# dast.net
KiCad netlist of a schematic drawn in Altium Designer
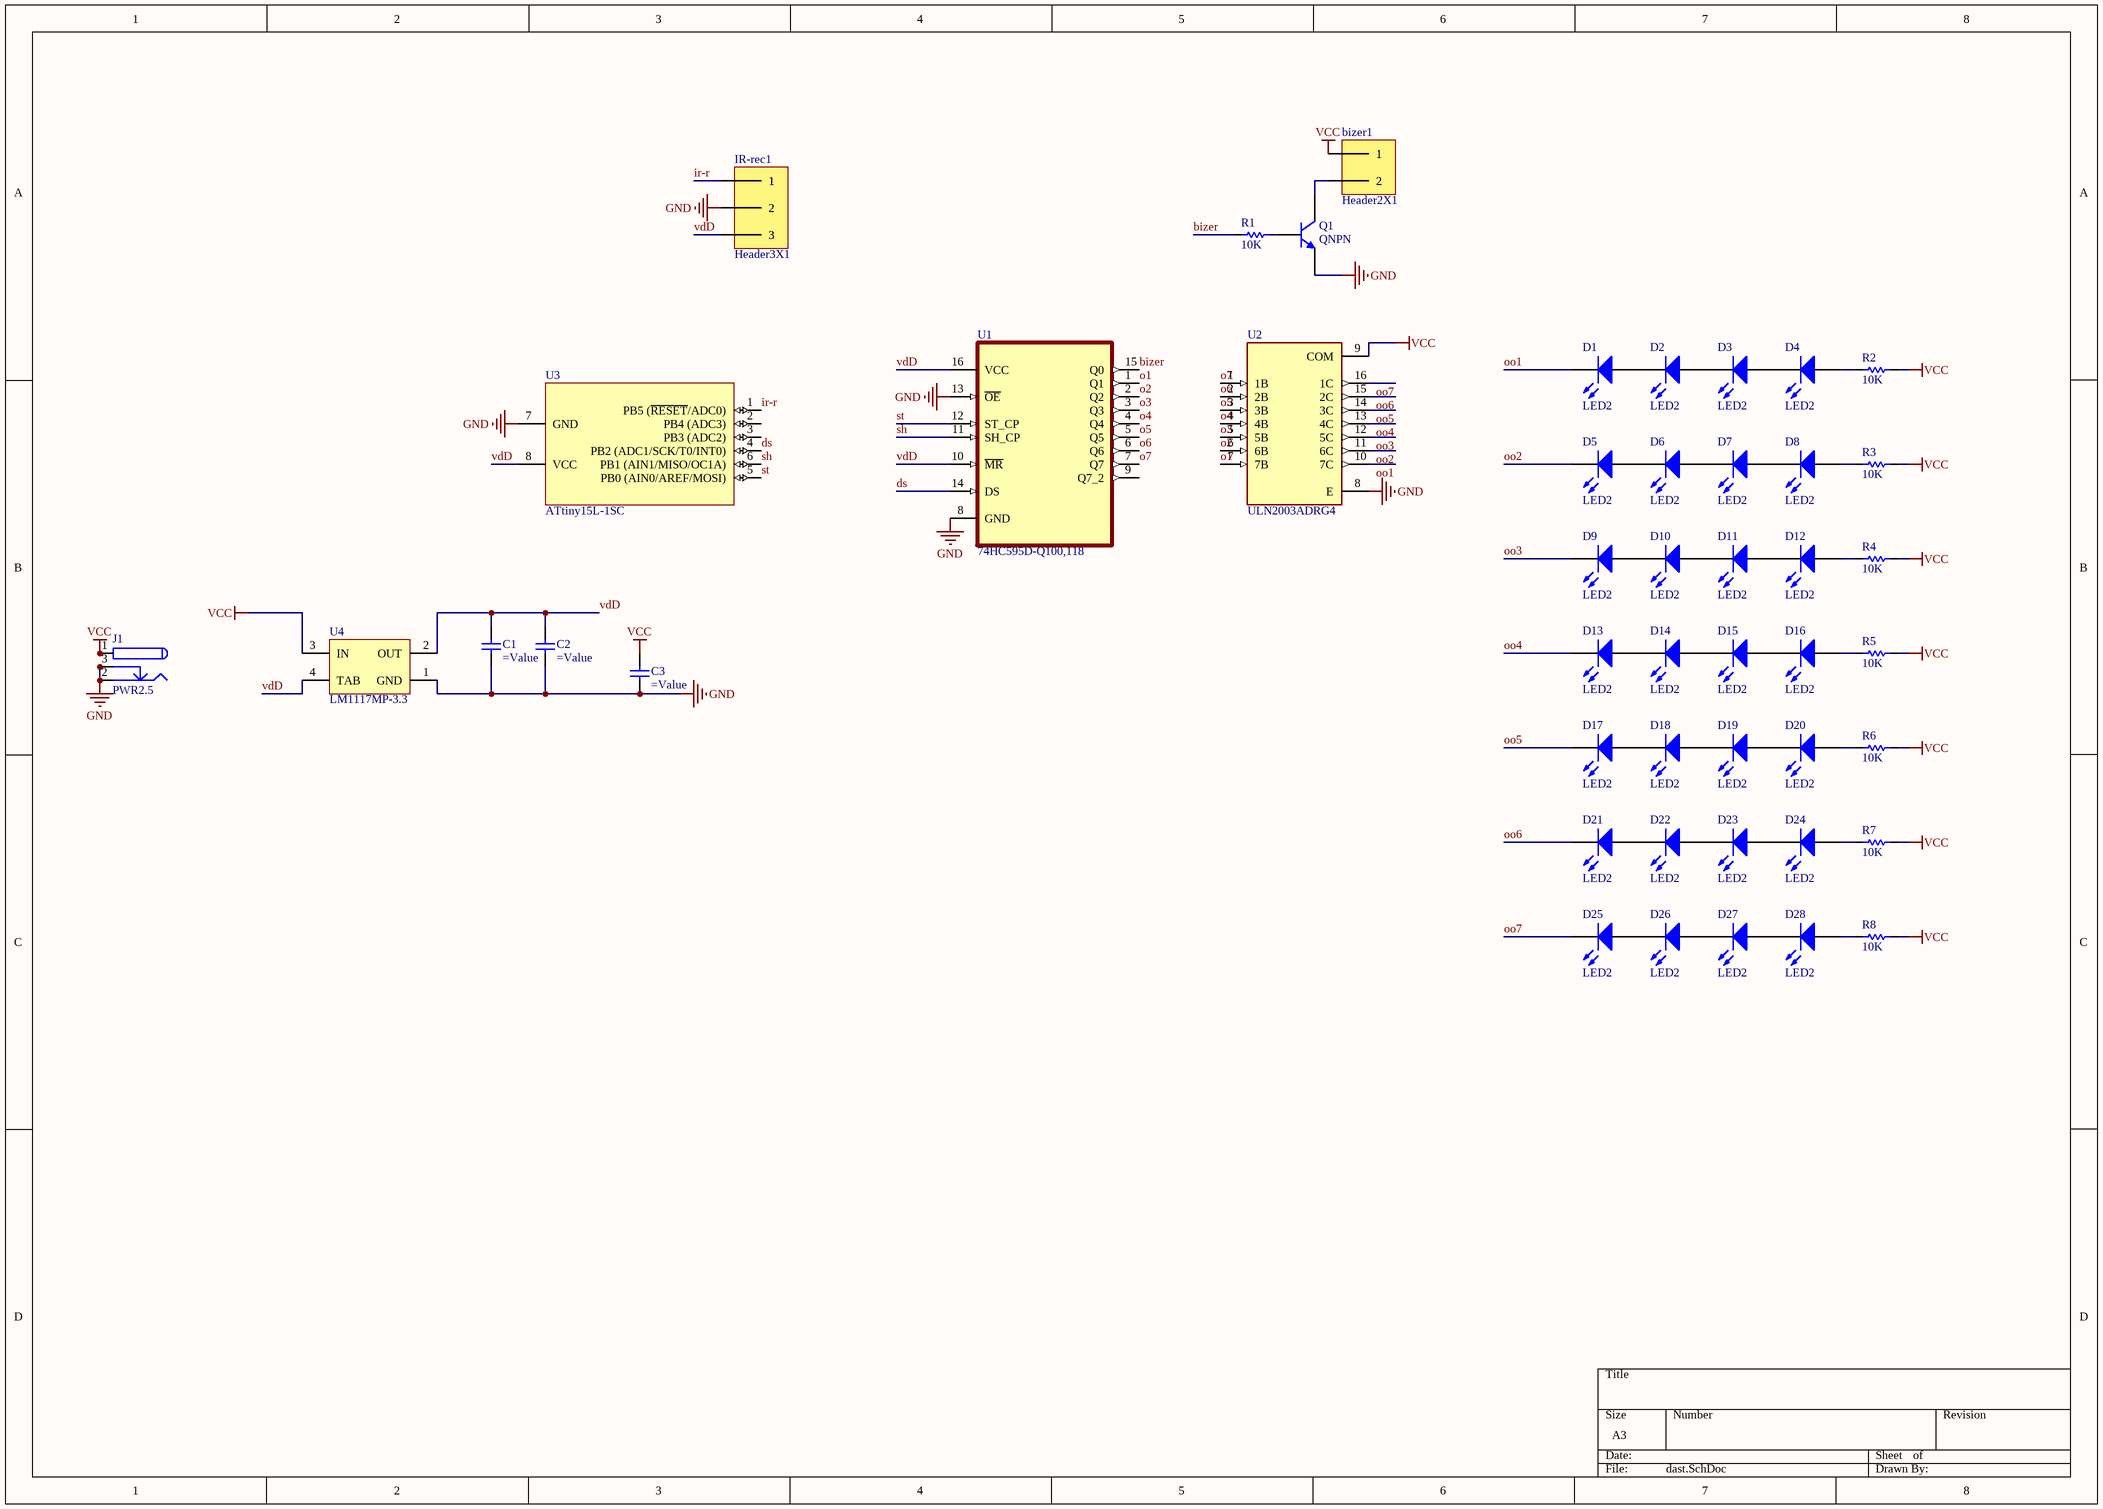
[diagram p0: dast.SchDoc]

(export (version "E")
  (design (tool "Eeschema 10.0.6"))
  (components
    (comp (ref "bizer1")
      (value "Header2X1")
      (footprint "Header 2X1")
      (libsource (lib "AltiumLib1") (part "Header2X1"))
    )
    (comp (ref "C1")
      (value "~")
      (footprint "CAP 1206")
      (description "Capacitor")
      (libsource (lib "AltiumLib1") (part "Capacitor"))
    )
    (comp (ref "C2")
      (value "~")
      (footprint "CAP 1206")
      (description "Capacitor")
      (libsource (lib "AltiumLib1") (part "Capacitor"))
    )
    (comp (ref "C3")
      (value "~")
      (footprint "CAP 1206")
      (description "Capacitor")
      (libsource (lib "AltiumLib1") (part "Capacitor"))
    )
    (comp (ref "D1")
      (value "LED2")
      (footprint "3.2X1.6X1.1")
      (description "Typical RED, GREEN, YELLOW, AMBER GaAs LED")
      (fields (field (name "PUBLISHER") "Altium Limited"))
      (libsource (lib "Miscellaneous Devices") (part "LED2"))
    )
    (comp (ref "D2")
      (value "LED2")
      (footprint "3.2X1.6X1.1")
      (description "Typical RED, GREEN, YELLOW, AMBER GaAs LED")
      (fields (field (name "PUBLISHER") "Altium Limited"))
      (libsource (lib "Miscellaneous Devices") (part "LED2"))
    )
    (comp (ref "D3")
      (value "LED2")
      (footprint "3.2X1.6X1.1")
      (description "Typical RED, GREEN, YELLOW, AMBER GaAs LED")
      (fields (field (name "PUBLISHER") "Altium Limited"))
      (libsource (lib "Miscellaneous Devices") (part "LED2"))
    )
    (comp (ref "D4")
      (value "LED2")
      (footprint "3.2X1.6X1.1")
      (description "Typical RED, GREEN, YELLOW, AMBER GaAs LED")
      (fields (field (name "PUBLISHER") "Altium Limited"))
      (libsource (lib "Miscellaneous Devices") (part "LED2"))
    )
    (comp (ref "D5")
      (value "LED2")
      (footprint "3.2X1.6X1.1")
      (description "Typical RED, GREEN, YELLOW, AMBER GaAs LED")
      (fields (field (name "PUBLISHER") "Altium Limited"))
      (libsource (lib "Miscellaneous Devices") (part "LED2"))
    )
    (comp (ref "D6")
      (value "LED2")
      (footprint "3.2X1.6X1.1")
      (description "Typical RED, GREEN, YELLOW, AMBER GaAs LED")
      (fields (field (name "PUBLISHER") "Altium Limited"))
      (libsource (lib "Miscellaneous Devices") (part "LED2"))
    )
    (comp (ref "D7")
      (value "LED2")
      (footprint "3.2X1.6X1.1")
      (description "Typical RED, GREEN, YELLOW, AMBER GaAs LED")
      (fields (field (name "PUBLISHER") "Altium Limited"))
      (libsource (lib "Miscellaneous Devices") (part "LED2"))
    )
    (comp (ref "D8")
      (value "LED2")
      (footprint "3.2X1.6X1.1")
      (description "Typical RED, GREEN, YELLOW, AMBER GaAs LED")
      (fields (field (name "PUBLISHER") "Altium Limited"))
      (libsource (lib "Miscellaneous Devices") (part "LED2"))
    )
    (comp (ref "D9")
      (value "LED2")
      (footprint "3.2X1.6X1.1")
      (description "Typical RED, GREEN, YELLOW, AMBER GaAs LED")
      (fields (field (name "PUBLISHER") "Altium Limited"))
      (libsource (lib "Miscellaneous Devices") (part "LED2"))
    )
    (comp (ref "D10")
      (value "LED2")
      (footprint "3.2X1.6X1.1")
      (description "Typical RED, GREEN, YELLOW, AMBER GaAs LED")
      (fields (field (name "PUBLISHER") "Altium Limited"))
      (libsource (lib "Miscellaneous Devices") (part "LED2"))
    )
    (comp (ref "D11")
      (value "LED2")
      (footprint "3.2X1.6X1.1")
      (description "Typical RED, GREEN, YELLOW, AMBER GaAs LED")
      (fields (field (name "PUBLISHER") "Altium Limited"))
      (libsource (lib "Miscellaneous Devices") (part "LED2"))
    )
    (comp (ref "D12")
      (value "LED2")
      (footprint "3.2X1.6X1.1")
      (description "Typical RED, GREEN, YELLOW, AMBER GaAs LED")
      (fields (field (name "PUBLISHER") "Altium Limited"))
      (libsource (lib "Miscellaneous Devices") (part "LED2"))
    )
    (comp (ref "D13")
      (value "LED2")
      (footprint "3.2X1.6X1.1")
      (description "Typical RED, GREEN, YELLOW, AMBER GaAs LED")
      (fields (field (name "PUBLISHER") "Altium Limited"))
      (libsource (lib "Miscellaneous Devices") (part "LED2"))
    )
    (comp (ref "D14")
      (value "LED2")
      (footprint "3.2X1.6X1.1")
      (description "Typical RED, GREEN, YELLOW, AMBER GaAs LED")
      (fields (field (name "PUBLISHER") "Altium Limited"))
      (libsource (lib "Miscellaneous Devices") (part "LED2"))
    )
    (comp (ref "D15")
      (value "LED2")
      (footprint "3.2X1.6X1.1")
      (description "Typical RED, GREEN, YELLOW, AMBER GaAs LED")
      (fields (field (name "PUBLISHER") "Altium Limited"))
      (libsource (lib "Miscellaneous Devices") (part "LED2"))
    )
    (comp (ref "D16")
      (value "LED2")
      (footprint "3.2X1.6X1.1")
      (description "Typical RED, GREEN, YELLOW, AMBER GaAs LED")
      (fields (field (name "PUBLISHER") "Altium Limited"))
      (libsource (lib "Miscellaneous Devices") (part "LED2"))
    )
    (comp (ref "D17")
      (value "LED2")
      (footprint "3.2X1.6X1.1")
      (description "Typical RED, GREEN, YELLOW, AMBER GaAs LED")
      (fields (field (name "PUBLISHER") "Altium Limited"))
      (libsource (lib "Miscellaneous Devices") (part "LED2"))
    )
    (comp (ref "D18")
      (value "LED2")
      (footprint "3.2X1.6X1.1")
      (description "Typical RED, GREEN, YELLOW, AMBER GaAs LED")
      (fields (field (name "PUBLISHER") "Altium Limited"))
      (libsource (lib "Miscellaneous Devices") (part "LED2"))
    )
    (comp (ref "D19")
      (value "LED2")
      (footprint "3.2X1.6X1.1")
      (description "Typical RED, GREEN, YELLOW, AMBER GaAs LED")
      (fields (field (name "PUBLISHER") "Altium Limited"))
      (libsource (lib "Miscellaneous Devices") (part "LED2"))
    )
    (comp (ref "D20")
      (value "LED2")
      (footprint "3.2X1.6X1.1")
      (description "Typical RED, GREEN, YELLOW, AMBER GaAs LED")
      (fields (field (name "PUBLISHER") "Altium Limited"))
      (libsource (lib "Miscellaneous Devices") (part "LED2"))
    )
    (comp (ref "D21")
      (value "LED2")
      (footprint "3.2X1.6X1.1")
      (description "Typical RED, GREEN, YELLOW, AMBER GaAs LED")
      (fields (field (name "PUBLISHER") "Altium Limited"))
      (libsource (lib "Miscellaneous Devices") (part "LED2"))
    )
    (comp (ref "D22")
      (value "LED2")
      (footprint "3.2X1.6X1.1")
      (description "Typical RED, GREEN, YELLOW, AMBER GaAs LED")
      (fields (field (name "PUBLISHER") "Altium Limited"))
      (libsource (lib "Miscellaneous Devices") (part "LED2"))
    )
    (comp (ref "D23")
      (value "LED2")
      (footprint "3.2X1.6X1.1")
      (description "Typical RED, GREEN, YELLOW, AMBER GaAs LED")
      (fields (field (name "PUBLISHER") "Altium Limited"))
      (libsource (lib "Miscellaneous Devices") (part "LED2"))
    )
    (comp (ref "D24")
      (value "LED2")
      (footprint "3.2X1.6X1.1")
      (description "Typical RED, GREEN, YELLOW, AMBER GaAs LED")
      (fields (field (name "PUBLISHER") "Altium Limited"))
      (libsource (lib "Miscellaneous Devices") (part "LED2"))
    )
    (comp (ref "D25")
      (value "LED2")
      (footprint "3.2X1.6X1.1")
      (description "Typical RED, GREEN, YELLOW, AMBER GaAs LED")
      (fields (field (name "PUBLISHER") "Altium Limited"))
      (libsource (lib "Miscellaneous Devices") (part "LED2"))
    )
    (comp (ref "D26")
      (value "LED2")
      (footprint "3.2X1.6X1.1")
      (description "Typical RED, GREEN, YELLOW, AMBER GaAs LED")
      (fields (field (name "PUBLISHER") "Altium Limited"))
      (libsource (lib "Miscellaneous Devices") (part "LED2"))
    )
    (comp (ref "D27")
      (value "LED2")
      (footprint "3.2X1.6X1.1")
      (description "Typical RED, GREEN, YELLOW, AMBER GaAs LED")
      (fields (field (name "PUBLISHER") "Altium Limited"))
      (libsource (lib "Miscellaneous Devices") (part "LED2"))
    )
    (comp (ref "D28")
      (value "LED2")
      (footprint "3.2X1.6X1.1")
      (description "Typical RED, GREEN, YELLOW, AMBER GaAs LED")
      (fields (field (name "PUBLISHER") "Altium Limited"))
      (libsource (lib "Miscellaneous Devices") (part "LED2"))
    )
    (comp (ref "IR-rec1")
      (value "Header3X1")
      (footprint "HEADER 3X1")
      (libsource (lib "AltiumLib1") (part "Header3X1"))
    )
    (comp (ref "J1")
      (value "PWR2.5")
      (footprint "KLD-0202")
      (description "Low Voltage Power Supply Connector")
      (fields (field (name "PUBLISHER") "Altium Limited"))
      (libsource (lib "Miscellaneous Connectors") (part "PWR2.5"))
    )
    (comp (ref "Q1")
      (value "QNPN")
      (footprint "SOT-23B_L")
      (description "NPN Bipolar Transistor")
      (fields (field (name "PUBLISHER") "Altium Limited"))
      (libsource (lib "Miscellaneous Devices") (part "QNPN"))
    )
    (comp (ref "R1")
      (value "10K")
      (footprint "RES 1206 (3216X08L)")
      (description "Resistor")
      (fields (field (name "TOLERANCE") "5%") (field (name "POWER") "1/4 W"))
      (libsource (lib "AltiumLib1") (part "Resistor"))
    )
    (comp (ref "R2")
      (value "10K")
      (footprint "RES 1206 (3216X08L)")
      (description "Resistor")
      (fields (field (name "TOLERANCE") "5%") (field (name "POWER") "1/4 W"))
      (libsource (lib "AltiumLib1") (part "Resistor"))
    )
    (comp (ref "R3")
      (value "10K")
      (footprint "RES 1206 (3216X08L)")
      (description "Resistor")
      (fields (field (name "TOLERANCE") "5%") (field (name "POWER") "1/4 W"))
      (libsource (lib "AltiumLib1") (part "Resistor"))
    )
    (comp (ref "R4")
      (value "10K")
      (footprint "RES 1206 (3216X08L)")
      (description "Resistor")
      (fields (field (name "TOLERANCE") "5%") (field (name "POWER") "1/4 W"))
      (libsource (lib "AltiumLib1") (part "Resistor"))
    )
    (comp (ref "R5")
      (value "10K")
      (footprint "RES 1206 (3216X08L)")
      (description "Resistor")
      (fields (field (name "TOLERANCE") "5%") (field (name "POWER") "1/4 W"))
      (libsource (lib "AltiumLib1") (part "Resistor"))
    )
    (comp (ref "R6")
      (value "10K")
      (footprint "RES 1206 (3216X08L)")
      (description "Resistor")
      (fields (field (name "TOLERANCE") "5%") (field (name "POWER") "1/4 W"))
      (libsource (lib "AltiumLib1") (part "Resistor"))
    )
    (comp (ref "R7")
      (value "10K")
      (footprint "RES 1206 (3216X08L)")
      (description "Resistor")
      (fields (field (name "TOLERANCE") "5%") (field (name "POWER") "1/4 W"))
      (libsource (lib "AltiumLib1") (part "Resistor"))
    )
    (comp (ref "R8")
      (value "10K")
      (footprint "RES 1206 (3216X08L)")
      (description "Resistor")
      (fields (field (name "TOLERANCE") "5%") (field (name "POWER") "1/4 W"))
      (libsource (lib "AltiumLib1") (part "Resistor"))
    )
    (comp (ref "U1")
      (value "74HC595D-Q100,118")
      (footprint "SOIC127P600X175-16N")
      (description "Shift Shift Register 1 Element 8 Bit 16-SO")
      (fields (field (name "MF") "Nexperia USA"))
      (libsource (lib "74HC595D-Q100_118") (part "74HC595D-Q100,118"))
    )
    (comp (ref "U2")
      (value "ULN2003ADRG4")
      (footprint "SOIC127P600X175-16N")
      (description "50-V, 7-ch darlington transistor array, -20C to 70C 16-SOIC -40 to 70")
      (libsource (lib "ULN2003ADRG4") (part "ULN2003ADRG4"))
    )
    (comp (ref "U3")
      (value "ATtiny15L-1SC")
      (footprint "8S2_N")
      (description "8-Bit AVR Microcontroller with 1K Byte of Flash Memory")
      (fields (field (name "PUBLISHER") "Altium Limited"))
      (libsource (lib "Atmel Microcontroller 8-Bit AVR") (part "ATtiny15L-1SC"))
    )
    (comp (ref "U4")
      (value "LM1117MP-3.3")
      (footprint "MP04A_N")
      (description "800mA Low-Dropout Linear Regulator")
      (fields
        (field (name "MANUFACTURER") "National Semiconductor")
        (field (name "DIGIKEYPARTNUMBER") "LM1117MP-3.3CT-ND")
        (field (name "PUBLISHER") "Altium Limited")
      )
      (libsource (lib "NSC LDO") (part "LM1117MP-3.3"))
    )
  )
  (nets
    (net (code "1") (name "/bizer") (class "Default")
      (node (ref "R1") (pin "1") (pinfunction "1_1") (pintype "passive"))
      (node (ref "U1") (pin "15") (pinfunction "Q0_15") (pintype "output"))
    )
    (net (code "2") (name "/ds") (class "Default")
      (node (ref "U1") (pin "14") (pinfunction "DS_14") (pintype "input"))
      (node (ref "U3") (pin "4") (pinfunction "PB2_(ADC1/SCK/T0/INT0)_4") (pintype "bidirectional"))
    )
    (net (code "3") (name "/ir-r") (class "Default")
      (node (ref "IR-rec1") (pin "1") (pinfunction "1_1") (pintype "passive"))
      (node (ref "U3") (pin "1") (pinfunction "PB5_(~{RESET}/ADC0)_1") (pintype "bidirectional"))
    )
    (net (code "4") (name "/o1") (class "Default")
      (node (ref "U1") (pin "1") (pinfunction "Q1_1") (pintype "output"))
      (node (ref "U2") (pin "7") (pinfunction "7B_7") (pintype "input"))
    )
    (net (code "5") (name "/o2") (class "Default")
      (node (ref "U1") (pin "2") (pinfunction "Q2_2") (pintype "output"))
      (node (ref "U2") (pin "6") (pinfunction "6B_6") (pintype "input"))
    )
    (net (code "6") (name "/o3") (class "Default")
      (node (ref "U1") (pin "3") (pinfunction "Q3_3") (pintype "output"))
      (node (ref "U2") (pin "5") (pinfunction "5B_5") (pintype "input"))
    )
    (net (code "7") (name "/o4") (class "Default")
      (node (ref "U1") (pin "4") (pinfunction "Q4_4") (pintype "output"))
      (node (ref "U2") (pin "4") (pinfunction "4B_4") (pintype "input"))
    )
    (net (code "8") (name "/o5") (class "Default")
      (node (ref "U1") (pin "5") (pinfunction "Q5_5") (pintype "output"))
      (node (ref "U2") (pin "3") (pinfunction "3B_3") (pintype "input"))
    )
    (net (code "9") (name "/o6") (class "Default")
      (node (ref "U1") (pin "6") (pinfunction "Q6_6") (pintype "output"))
      (node (ref "U2") (pin "2") (pinfunction "2B_2") (pintype "input"))
    )
    (net (code "10") (name "/o7") (class "Default")
      (node (ref "U1") (pin "7") (pinfunction "Q7_7") (pintype "output"))
      (node (ref "U2") (pin "1") (pinfunction "1B_1") (pintype "input"))
    )
    (net (code "11") (name "/oo1") (class "Default")
      (node (ref "D1") (pin "2") (pinfunction "K_2") (pintype "passive"))
      (node (ref "U2") (pin "10") (pinfunction "7C_10") (pintype "output"))
    )
    (net (code "12") (name "/oo2") (class "Default")
      (node (ref "D5") (pin "2") (pinfunction "K_2") (pintype "passive"))
      (node (ref "U2") (pin "11") (pinfunction "6C_11") (pintype "output"))
    )
    (net (code "13") (name "/oo3") (class "Default")
      (node (ref "D9") (pin "2") (pinfunction "K_2") (pintype "passive"))
      (node (ref "U2") (pin "12") (pinfunction "5C_12") (pintype "output"))
    )
    (net (code "14") (name "/oo4") (class "Default")
      (node (ref "D13") (pin "2") (pinfunction "K_2") (pintype "passive"))
      (node (ref "U2") (pin "13") (pinfunction "4C_13") (pintype "output"))
    )
    (net (code "15") (name "/oo5") (class "Default")
      (node (ref "D17") (pin "2") (pinfunction "K_2") (pintype "passive"))
      (node (ref "U2") (pin "14") (pinfunction "3C_14") (pintype "output"))
    )
    (net (code "16") (name "/oo6") (class "Default")
      (node (ref "D21") (pin "2") (pinfunction "K_2") (pintype "passive"))
      (node (ref "U2") (pin "15") (pinfunction "2C_15") (pintype "output"))
    )
    (net (code "17") (name "/oo7") (class "Default")
      (node (ref "D25") (pin "2") (pinfunction "K_2") (pintype "passive"))
      (node (ref "U2") (pin "16") (pinfunction "1C_16") (pintype "output"))
    )
    (net (code "18") (name "/sh") (class "Default")
      (node (ref "U1") (pin "11") (pinfunction "SH_CP_11") (pintype "input"))
      (node (ref "U3") (pin "6") (pinfunction "PB1_(AIN1/MISO/OC1A)_6") (pintype "bidirectional"))
    )
    (net (code "19") (name "/st") (class "Default")
      (node (ref "U1") (pin "12") (pinfunction "ST_CP_12") (pintype "input"))
      (node (ref "U3") (pin "5") (pinfunction "PB0_(AIN0/AREF/MOSI)_5") (pintype "bidirectional"))
    )
    (net (code "20") (name "/vdD") (class "Default")
      (node (ref "C1") (pin "2") (pinfunction "-_2") (pintype "passive"))
      (node (ref "C2") (pin "2") (pinfunction "-_2") (pintype "passive"))
      (node (ref "IR-rec1") (pin "3") (pinfunction "3_3") (pintype "passive"))
      (node (ref "U1") (pin "10") (pinfunction "~{MR}_10") (pintype "input"))
      (node (ref "U1") (pin "16") (pinfunction "VCC_16") (pintype "power_in"))
      (node (ref "U3") (pin "8") (pinfunction "VCC_8") (pintype "power_in"))
      (node (ref "U4") (pin "2") (pinfunction "OUT_2") (pintype "power_in"))
      (node (ref "U4") (pin "4") (pinfunction "TAB_4") (pintype "power_in"))
    )
    (net (code "21") (name "GND") (class "Default")
      (node (ref "C1") (pin "1") (pinfunction "+_1") (pintype "passive"))
      (node (ref "C2") (pin "1") (pinfunction "+_1") (pintype "passive"))
      (node (ref "C3") (pin "1") (pinfunction "+_1") (pintype "passive"))
      (node (ref "IR-rec1") (pin "2") (pinfunction "2_2") (pintype "passive"))
      (node (ref "J1") (pin "2") (pinfunction "2_2") (pintype "power_in"))
      (node (ref "J1") (pin "2A") (pinfunction "2A_2A") (pintype "power_in"))
      (node (ref "J1") (pin "2B") (pinfunction "2B_2B") (pintype "power_in"))
      (node (ref "J1") (pin "3") (pinfunction "3_3") (pintype "power_in"))
      (node (ref "J1") (pin "3A") (pinfunction "3A_3A") (pintype "power_in"))
      (node (ref "J1") (pin "3B") (pinfunction "3B_3B") (pintype "power_in"))
      (node (ref "Q1") (pin "3") (pinfunction "E_3") (pintype "passive"))
      (node (ref "U1") (pin "13") (pinfunction "~{OE}_13") (pintype "input"))
      (node (ref "U1") (pin "8") (pinfunction "GND_8") (pintype "passive"))
      (node (ref "U2") (pin "8") (pinfunction "E_8") (pintype "passive"))
      (node (ref "U3") (pin "7") (pinfunction "GND_7") (pintype "power_in"))
      (node (ref "U4") (pin "1") (pinfunction "GND_1") (pintype "power_in"))
    )
    (net (code "22") (name "Net-(D1-A)") (class "Default")
      (node (ref "D1") (pin "1") (pinfunction "A_1") (pintype "passive"))
      (node (ref "D2") (pin "2") (pinfunction "K_2") (pintype "passive"))
    )
    (net (code "23") (name "Net-(D2-A)") (class "Default")
      (node (ref "D2") (pin "1") (pinfunction "A_1") (pintype "passive"))
      (node (ref "D3") (pin "2") (pinfunction "K_2") (pintype "passive"))
    )
    (net (code "24") (name "Net-(D3-A)") (class "Default")
      (node (ref "D3") (pin "1") (pinfunction "A_1") (pintype "passive"))
      (node (ref "D4") (pin "2") (pinfunction "K_2") (pintype "passive"))
    )
    (net (code "25") (name "Net-(D4-A)") (class "Default")
      (node (ref "D4") (pin "1") (pinfunction "A_1") (pintype "passive"))
      (node (ref "R2") (pin "1") (pinfunction "1_1") (pintype "passive"))
    )
    (net (code "26") (name "Net-(D5-A)") (class "Default")
      (node (ref "D5") (pin "1") (pinfunction "A_1") (pintype "passive"))
      (node (ref "D6") (pin "2") (pinfunction "K_2") (pintype "passive"))
    )
    (net (code "27") (name "Net-(D6-A)") (class "Default")
      (node (ref "D6") (pin "1") (pinfunction "A_1") (pintype "passive"))
      (node (ref "D7") (pin "2") (pinfunction "K_2") (pintype "passive"))
    )
    (net (code "28") (name "Net-(D7-A)") (class "Default")
      (node (ref "D7") (pin "1") (pinfunction "A_1") (pintype "passive"))
      (node (ref "D8") (pin "2") (pinfunction "K_2") (pintype "passive"))
    )
    (net (code "29") (name "Net-(D8-A)") (class "Default")
      (node (ref "D8") (pin "1") (pinfunction "A_1") (pintype "passive"))
      (node (ref "R3") (pin "1") (pinfunction "1_1") (pintype "passive"))
    )
    (net (code "30") (name "Net-(D10-A)") (class "Default")
      (node (ref "D10") (pin "1") (pinfunction "A_1") (pintype "passive"))
      (node (ref "D11") (pin "2") (pinfunction "K_2") (pintype "passive"))
    )
    (net (code "31") (name "Net-(D10-K)") (class "Default")
      (node (ref "D10") (pin "2") (pinfunction "K_2") (pintype "passive"))
      (node (ref "D9") (pin "1") (pinfunction "A_1") (pintype "passive"))
    )
    (net (code "32") (name "Net-(D11-A)") (class "Default")
      (node (ref "D11") (pin "1") (pinfunction "A_1") (pintype "passive"))
      (node (ref "D12") (pin "2") (pinfunction "K_2") (pintype "passive"))
    )
    (net (code "33") (name "Net-(D12-A)") (class "Default")
      (node (ref "D12") (pin "1") (pinfunction "A_1") (pintype "passive"))
      (node (ref "R4") (pin "1") (pinfunction "1_1") (pintype "passive"))
    )
    (net (code "34") (name "Net-(D13-A)") (class "Default")
      (node (ref "D13") (pin "1") (pinfunction "A_1") (pintype "passive"))
      (node (ref "D14") (pin "2") (pinfunction "K_2") (pintype "passive"))
    )
    (net (code "35") (name "Net-(D14-A)") (class "Default")
      (node (ref "D14") (pin "1") (pinfunction "A_1") (pintype "passive"))
      (node (ref "D15") (pin "2") (pinfunction "K_2") (pintype "passive"))
    )
    (net (code "36") (name "Net-(D15-A)") (class "Default")
      (node (ref "D15") (pin "1") (pinfunction "A_1") (pintype "passive"))
      (node (ref "D16") (pin "2") (pinfunction "K_2") (pintype "passive"))
    )
    (net (code "37") (name "Net-(D16-A)") (class "Default")
      (node (ref "D16") (pin "1") (pinfunction "A_1") (pintype "passive"))
      (node (ref "R5") (pin "1") (pinfunction "1_1") (pintype "passive"))
    )
    (net (code "38") (name "Net-(D17-A)") (class "Default")
      (node (ref "D17") (pin "1") (pinfunction "A_1") (pintype "passive"))
      (node (ref "D18") (pin "2") (pinfunction "K_2") (pintype "passive"))
    )
    (net (code "39") (name "Net-(D18-A)") (class "Default")
      (node (ref "D18") (pin "1") (pinfunction "A_1") (pintype "passive"))
      (node (ref "D19") (pin "2") (pinfunction "K_2") (pintype "passive"))
    )
    (net (code "40") (name "Net-(D19-A)") (class "Default")
      (node (ref "D19") (pin "1") (pinfunction "A_1") (pintype "passive"))
      (node (ref "D20") (pin "2") (pinfunction "K_2") (pintype "passive"))
    )
    (net (code "41") (name "Net-(D20-A)") (class "Default")
      (node (ref "D20") (pin "1") (pinfunction "A_1") (pintype "passive"))
      (node (ref "R6") (pin "1") (pinfunction "1_1") (pintype "passive"))
    )
    (net (code "42") (name "Net-(D21-A)") (class "Default")
      (node (ref "D21") (pin "1") (pinfunction "A_1") (pintype "passive"))
      (node (ref "D22") (pin "2") (pinfunction "K_2") (pintype "passive"))
    )
    (net (code "43") (name "Net-(D22-A)") (class "Default")
      (node (ref "D22") (pin "1") (pinfunction "A_1") (pintype "passive"))
      (node (ref "D23") (pin "2") (pinfunction "K_2") (pintype "passive"))
    )
    (net (code "44") (name "Net-(D23-A)") (class "Default")
      (node (ref "D23") (pin "1") (pinfunction "A_1") (pintype "passive"))
      (node (ref "D24") (pin "2") (pinfunction "K_2") (pintype "passive"))
    )
    (net (code "45") (name "Net-(D24-A)") (class "Default")
      (node (ref "D24") (pin "1") (pinfunction "A_1") (pintype "passive"))
      (node (ref "R7") (pin "1") (pinfunction "1_1") (pintype "passive"))
    )
    (net (code "46") (name "Net-(D25-A)") (class "Default")
      (node (ref "D25") (pin "1") (pinfunction "A_1") (pintype "passive"))
      (node (ref "D26") (pin "2") (pinfunction "K_2") (pintype "passive"))
    )
    (net (code "47") (name "Net-(D26-A)") (class "Default")
      (node (ref "D26") (pin "1") (pinfunction "A_1") (pintype "passive"))
      (node (ref "D27") (pin "2") (pinfunction "K_2") (pintype "passive"))
    )
    (net (code "48") (name "Net-(D27-A)") (class "Default")
      (node (ref "D27") (pin "1") (pinfunction "A_1") (pintype "passive"))
      (node (ref "D28") (pin "2") (pinfunction "K_2") (pintype "passive"))
    )
    (net (code "49") (name "Net-(D28-A)") (class "Default")
      (node (ref "D28") (pin "1") (pinfunction "A_1") (pintype "passive"))
      (node (ref "R8") (pin "1") (pinfunction "1_1") (pintype "passive"))
    )
    (net (code "50") (name "Net-(Q1-B)") (class "Default")
      (node (ref "Q1") (pin "2") (pinfunction "B_2") (pintype "passive"))
      (node (ref "R1") (pin "2") (pinfunction "2_2") (pintype "passive"))
    )
    (net (code "51") (name "Net-(Q1-C)") (class "Default")
      (node (ref "Q1") (pin "1") (pinfunction "C_1") (pintype "passive"))
      (node (ref "bizer1") (pin "2") (pinfunction "2_2") (pintype "passive"))
    )
    (net (code "52") (name "VCC") (class "Default")
      (node (ref "C3") (pin "2") (pinfunction "-_2") (pintype "passive"))
      (node (ref "J1") (pin "1") (pinfunction "1_1") (pintype "power_in"))
      (node (ref "J1") (pin "1A") (pinfunction "1A_1A") (pintype "power_in"))
      (node (ref "J1") (pin "1B") (pinfunction "1B_1B") (pintype "power_in"))
      (node (ref "R2") (pin "2") (pinfunction "2_2") (pintype "passive"))
      (node (ref "R3") (pin "2") (pinfunction "2_2") (pintype "passive"))
      (node (ref "R4") (pin "2") (pinfunction "2_2") (pintype "passive"))
      (node (ref "R5") (pin "2") (pinfunction "2_2") (pintype "passive"))
      (node (ref "R6") (pin "2") (pinfunction "2_2") (pintype "passive"))
      (node (ref "R7") (pin "2") (pinfunction "2_2") (pintype "passive"))
      (node (ref "R8") (pin "2") (pinfunction "2_2") (pintype "passive"))
      (node (ref "U2") (pin "9") (pinfunction "COM_9") (pintype "power_in"))
      (node (ref "U4") (pin "3") (pinfunction "IN_3") (pintype "power_in"))
      (node (ref "bizer1") (pin "1") (pinfunction "1_1") (pintype "passive"))
    )
    (net (code "53") (name "unconnected-(U1-Q7_2-Pad9)") (class "Default")
      (node (ref "U1") (pin "9") (pinfunction "Q7_2_9") (pintype "output"))
    )
    (net (code "54") (name "unconnected-(U3-PB3_(ADC2)-Pad3)") (class "Default")
      (node (ref "U3") (pin "3") (pinfunction "PB3_(ADC2)_3") (pintype "bidirectional"))
    )
    (net (code "55") (name "unconnected-(U3-PB4_(ADC3)-Pad2)") (class "Default")
      (node (ref "U3") (pin "2") (pinfunction "PB4_(ADC3)_2") (pintype "bidirectional"))
    )
  )
)
